# breath_detector.net
KiCad netlist of a schematic drawn in Altium Designer
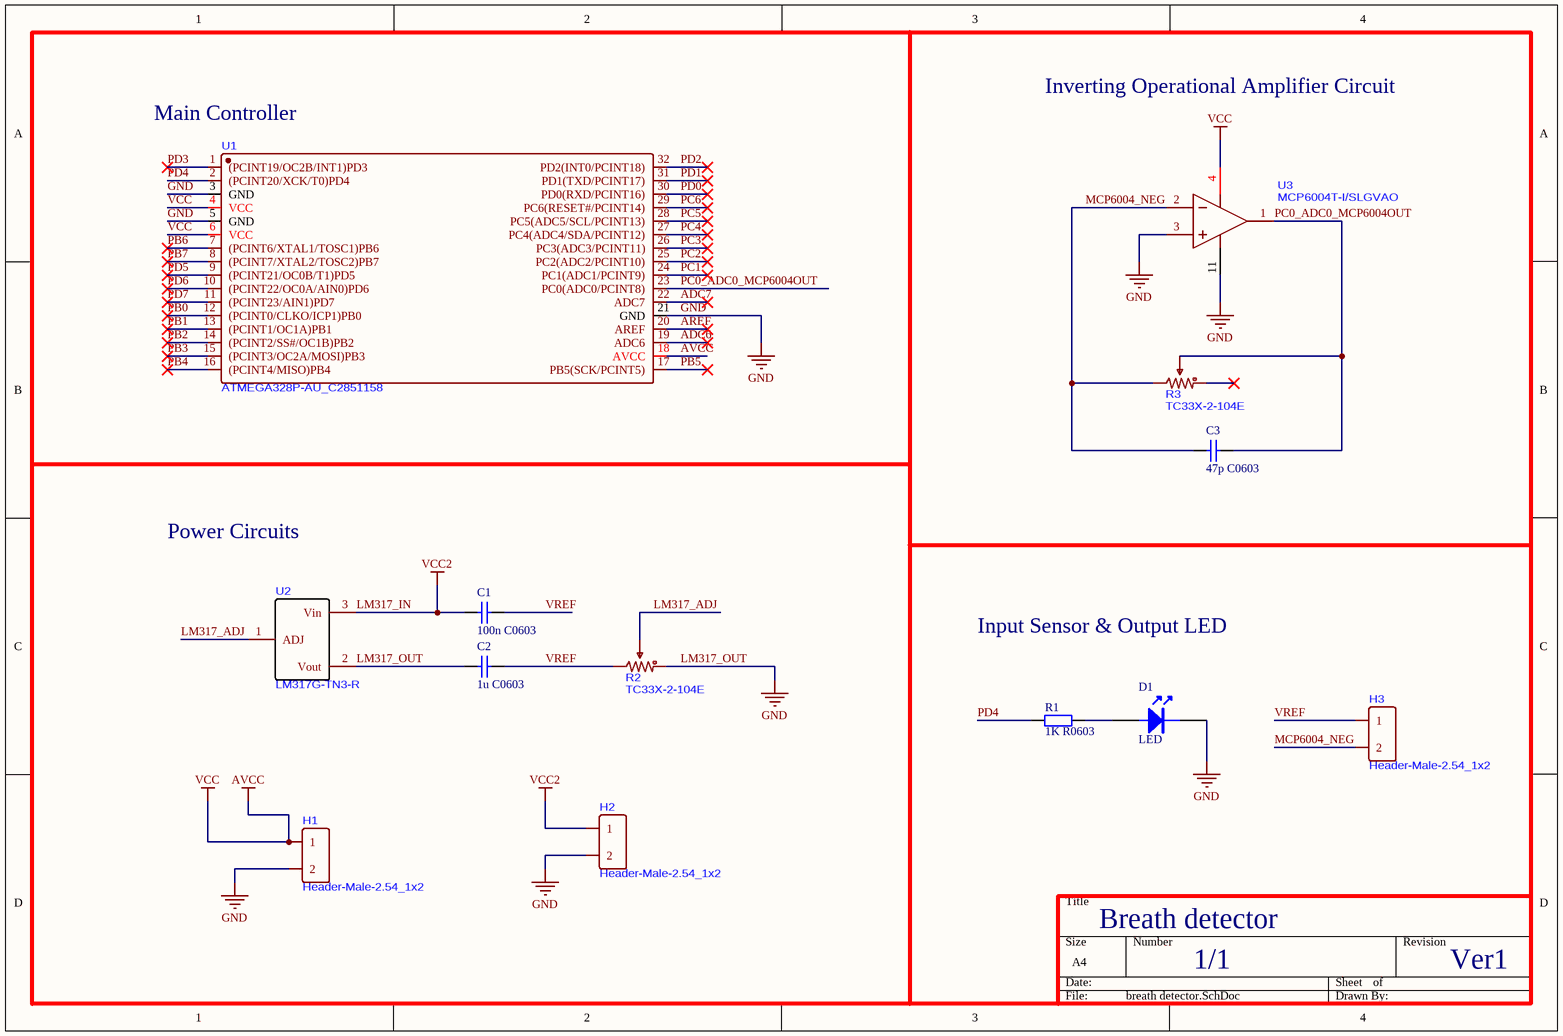
[diagram p0: breath detector.SchDoc]

(export (version "E")
  (design (tool "Eeschema 10.0.6"))
  (components
    (comp (ref "C1")
      (value "100n C0603")
      (footprint "C 0603")
      (fields (field (name "PUBLISHER") "Altium Limited"))
      (libsource (lib "breath detector") (part "Cap"))
    )
    (comp (ref "C2")
      (value "1u C0603")
      (footprint "C 0603")
      (fields (field (name "PUBLISHER") "Altium Limited"))
      (libsource (lib "breath detector") (part "Cap"))
    )
    (comp (ref "C3")
      (value "47p C0603")
      (footprint "C 0603")
      (fields (field (name "PUBLISHER") "Altium Limited"))
      (libsource (lib "breath detector") (part "Cap"))
    )
    (comp (ref "D1") (value "LED") (footprint "LED 0805G") (libsource (lib "breath detector") (part "LED")))
    (comp (ref "H1")
      (value "Header-Male-2.54_1x2")
      (footprint "HDR-TH_2P-P2.54-V-M-1")
      (libsource (lib "breath detector") (part "Header-Male-2.54_1x2"))
    )
    (comp (ref "H2")
      (value "Header-Male-2.54_1x2")
      (footprint "HDR-TH_2P-P2.54-V-M-1")
      (libsource (lib "breath detector") (part "Header-Male-2.54_1x2"))
    )
    (comp (ref "H3")
      (value "Header-Male-2.54_1x2")
      (footprint "HDR-TH_2P-P2.54-V-M-1")
      (libsource (lib "breath detector") (part "Header-Male-2.54_1x2"))
    )
    (comp (ref "R1")
      (value "1K R0603")
      (footprint "R 0603")
      (fields (field (name "PUBLISHER") "Altium Limited"))
      (libsource (lib "breath detector") (part "Res2"))
    )
    (comp (ref "R2")
      (value "TC33X-2-104E")
      (footprint "RES-ADJ-SMD_TC33X-2-104E")
      (libsource (lib "breath detector") (part "TC33X-2-104E"))
    )
    (comp (ref "R3")
      (value "TC33X-2-104E")
      (footprint "RES-ADJ-SMD_TC33X-2-104E")
      (libsource (lib "breath detector") (part "TC33X-2-104E"))
    )
    (comp (ref "U1")
      (value "ATMEGA328P-AU_C2851158")
      (footprint "TQFP-32_L7.0-W7.0-P0.80-LS9.0-BL")
      (libsource (lib "breath detector") (part "ATMEGA328P-AU_C2851158"))
    )
    (comp (ref "U2")
      (value "LM317G-TN3-R")
      (footprint "TO-252-2_L6.6-W6.1-P4.57-LS9.9-TL-CW")
      (libsource (lib "breath detector") (part "LM317G-TN3-R"))
    )
    (comp (ref "U3")
      (value "MCP6004T-I/SLGVAO")
      (footprint "SOIC-14_L8.7-W3.9-P1.27-LS6.0-BL")
      (libsource (lib "breath detector") (part "MCP6004T-I/SLGVAO"))
    )
  )
  (nets
    (net (code "1") (name "/ADC6") (class "Default")
      (node (ref "U1") (pin "19") (pinfunction "ADC6_19") (pintype "passive+no_connect"))
    )
    (net (code "2") (name "/ADC7") (class "Default")
      (node (ref "U1") (pin "22") (pinfunction "ADC7_22") (pintype "passive+no_connect"))
    )
    (net (code "3") (name "/AREF") (class "Default")
      (node (ref "U1") (pin "20") (pinfunction "AREF_20") (pintype "passive+no_connect"))
    )
    (net (code "4") (name "/LM317_ADJ") (class "Default")
      (node (ref "R2") (pin "2") (pinfunction "2_2") (pintype "passive"))
      (node (ref "U2") (pin "1") (pinfunction "ADJ_1") (pintype "passive"))
    )
    (net (code "5") (name "/MCP6004_NEG") (class "Default")
      (node (ref "C3") (pin "1") (pinfunction "1_1") (pintype "passive"))
      (node (ref "H3") (pin "2") (pinfunction "2_2") (pintype "passive"))
      (node (ref "R3") (pin "3") (pinfunction "3_3") (pintype "passive"))
      (node (ref "U3") (pin "2") (pinfunction "VIN_A-_2") (pintype "passive"))
    )
    (net (code "6") (name "/PB0") (class "Default")
      (node (ref "U1") (pin "12") (pinfunction "(PCINT0/CLKO/ICP1)PB0_12") (pintype "passive+no_connect"))
    )
    (net (code "7") (name "/PB1") (class "Default")
      (node (ref "U1") (pin "13") (pinfunction "(PCINT1/OC1A)PB1_13") (pintype "passive+no_connect"))
    )
    (net (code "8") (name "/PB2") (class "Default")
      (node (ref "U1") (pin "14") (pinfunction "(PCINT2/SS#/OC1B)PB2_14") (pintype "passive+no_connect"))
    )
    (net (code "9") (name "/PB3") (class "Default")
      (node (ref "U1") (pin "15") (pinfunction "(PCINT3/OC2A/MOSI)PB3_15") (pintype "passive+no_connect"))
    )
    (net (code "10") (name "/PB4") (class "Default")
      (node (ref "U1") (pin "16") (pinfunction "(PCINT4/MISO)PB4_16") (pintype "passive+no_connect"))
    )
    (net (code "11") (name "/PB5") (class "Default")
      (node (ref "U1") (pin "17") (pinfunction "PB5(SCK/PCINT5)_17") (pintype "passive+no_connect"))
    )
    (net (code "12") (name "/PB6") (class "Default")
      (node (ref "U1") (pin "7") (pinfunction "(PCINT6/XTAL1/TOSC1)PB6_7") (pintype "passive+no_connect"))
    )
    (net (code "13") (name "/PB7") (class "Default")
      (node (ref "U1") (pin "8") (pinfunction "(PCINT7/XTAL2/TOSC2)PB7_8") (pintype "passive+no_connect"))
    )
    (net (code "14") (name "/PC0_ADC0_MCP6004OUT") (class "Default")
      (node (ref "C3") (pin "2") (pinfunction "2_2") (pintype "passive"))
      (node (ref "R3") (pin "2") (pinfunction "2_2") (pintype "passive"))
      (node (ref "U1") (pin "23") (pinfunction "PC0(ADC0/PCINT8)_23") (pintype "passive"))
      (node (ref "U3") (pin "1") (pinfunction "VOUT_A_1") (pintype "passive"))
    )
    (net (code "15") (name "/PC1") (class "Default")
      (node (ref "U1") (pin "24") (pinfunction "PC1(ADC1/PCINT9)_24") (pintype "passive+no_connect"))
    )
    (net (code "16") (name "/PC2") (class "Default")
      (node (ref "U1") (pin "25") (pinfunction "PC2(ADC2/PCINT10)_25") (pintype "passive+no_connect"))
    )
    (net (code "17") (name "/PC3") (class "Default")
      (node (ref "U1") (pin "26") (pinfunction "PC3(ADC3/PCINT11)_26") (pintype "passive+no_connect"))
    )
    (net (code "18") (name "/PC4") (class "Default")
      (node (ref "U1") (pin "27") (pinfunction "PC4(ADC4/SDA/PCINT12)_27") (pintype "passive+no_connect"))
    )
    (net (code "19") (name "/PC5") (class "Default")
      (node (ref "U1") (pin "28") (pinfunction "PC5(ADC5/SCL/PCINT13)_28") (pintype "passive+no_connect"))
    )
    (net (code "20") (name "/PC6") (class "Default")
      (node (ref "U1") (pin "29") (pinfunction "PC6(RESET#/PCINT14)_29") (pintype "passive+no_connect"))
    )
    (net (code "21") (name "/PD0") (class "Default")
      (node (ref "U1") (pin "30") (pinfunction "PD0(RXD/PCINT16)_30") (pintype "passive+no_connect"))
    )
    (net (code "22") (name "/PD1") (class "Default")
      (node (ref "U1") (pin "31") (pinfunction "PD1(TXD/PCINT17)_31") (pintype "passive+no_connect"))
    )
    (net (code "23") (name "/PD2") (class "Default")
      (node (ref "U1") (pin "32") (pinfunction "PD2(INT0/PCINT18)_32") (pintype "passive+no_connect"))
    )
    (net (code "24") (name "/PD3") (class "Default")
      (node (ref "U1") (pin "1") (pinfunction "(PCINT19/OC2B/INT1)PD3_1") (pintype "passive+no_connect"))
    )
    (net (code "25") (name "/PD4") (class "Default")
      (node (ref "R1") (pin "1") (pinfunction "1_1") (pintype "passive"))
      (node (ref "U1") (pin "2") (pinfunction "(PCINT20/XCK/T0)PD4_2") (pintype "passive"))
    )
    (net (code "26") (name "/PD5") (class "Default")
      (node (ref "U1") (pin "9") (pinfunction "(PCINT21/OC0B/T1)PD5_9") (pintype "passive+no_connect"))
    )
    (net (code "27") (name "/PD6") (class "Default")
      (node (ref "U1") (pin "10") (pinfunction "(PCINT22/OC0A/AIN0)PD6_10") (pintype "passive+no_connect"))
    )
    (net (code "28") (name "/PD7") (class "Default")
      (node (ref "U1") (pin "11") (pinfunction "(PCINT23/AIN1)PD7_11") (pintype "passive+no_connect"))
    )
    (net (code "29") (name "/VREF") (class "Default")
      (node (ref "C1") (pin "2") (pinfunction "2_2") (pintype "passive"))
      (node (ref "C2") (pin "2") (pinfunction "2_2") (pintype "passive"))
      (node (ref "H3") (pin "1") (pinfunction "1_1") (pintype "passive"))
      (node (ref "R2") (pin "3") (pinfunction "3_3") (pintype "passive"))
    )
    (net (code "30") (name "AVCC") (class "Default")
      (node (ref "H1") (pin "1") (pinfunction "1_1") (pintype "passive"))
      (node (ref "U1") (pin "18") (pinfunction "AVCC_18") (pintype "passive"))
      (node (ref "U1") (pin "4") (pinfunction "VCC_4") (pintype "passive"))
      (node (ref "U1") (pin "6") (pinfunction "VCC_6") (pintype "passive"))
      (node (ref "U3") (pin "4") (pinfunction "VDD_4") (pintype "passive"))
    )
    (net (code "31") (name "GND") (class "Default")
      (node (ref "C2") (pin "1") (pinfunction "1_1") (pintype "passive"))
      (node (ref "D1") (pin "2") (pinfunction "2_2") (pintype "passive"))
      (node (ref "H1") (pin "2") (pinfunction "2_2") (pintype "passive"))
      (node (ref "H2") (pin "2") (pinfunction "2_2") (pintype "passive"))
      (node (ref "R2") (pin "1") (pinfunction "1_1") (pintype "passive"))
      (node (ref "U1") (pin "21") (pinfunction "GND_21") (pintype "passive"))
      (node (ref "U1") (pin "3") (pinfunction "GND_3") (pintype "passive"))
      (node (ref "U1") (pin "5") (pinfunction "GND_5") (pintype "passive"))
      (node (ref "U2") (pin "2") (pinfunction "Vout_2") (pintype "passive"))
      (node (ref "U3") (pin "11") (pinfunction "VSS_11") (pintype "passive"))
      (node (ref "U3") (pin "3") (pinfunction "VIN_A+_3") (pintype "passive"))
    )
    (net (code "32") (name "Net-(D1-Pad1)") (class "Default")
      (node (ref "D1") (pin "1") (pinfunction "1_1") (pintype "passive"))
      (node (ref "R1") (pin "2") (pinfunction "2_2") (pintype "passive"))
    )
    (net (code "33") (name "VCC2") (class "Default")
      (node (ref "C1") (pin "1") (pinfunction "1_1") (pintype "passive"))
      (node (ref "H2") (pin "1") (pinfunction "1_1") (pintype "passive"))
      (node (ref "U2") (pin "3") (pinfunction "Vin_3") (pintype "passive"))
    )
    (net (code "34") (name "unconnected-(R3-Pad1)") (class "Default")
      (node (ref "R3") (pin "1") (pinfunction "1_1") (pintype "passive+no_connect"))
    )
  )
)
